# POWER.net
KiCad netlist of a schematic drawn in Altium Designer
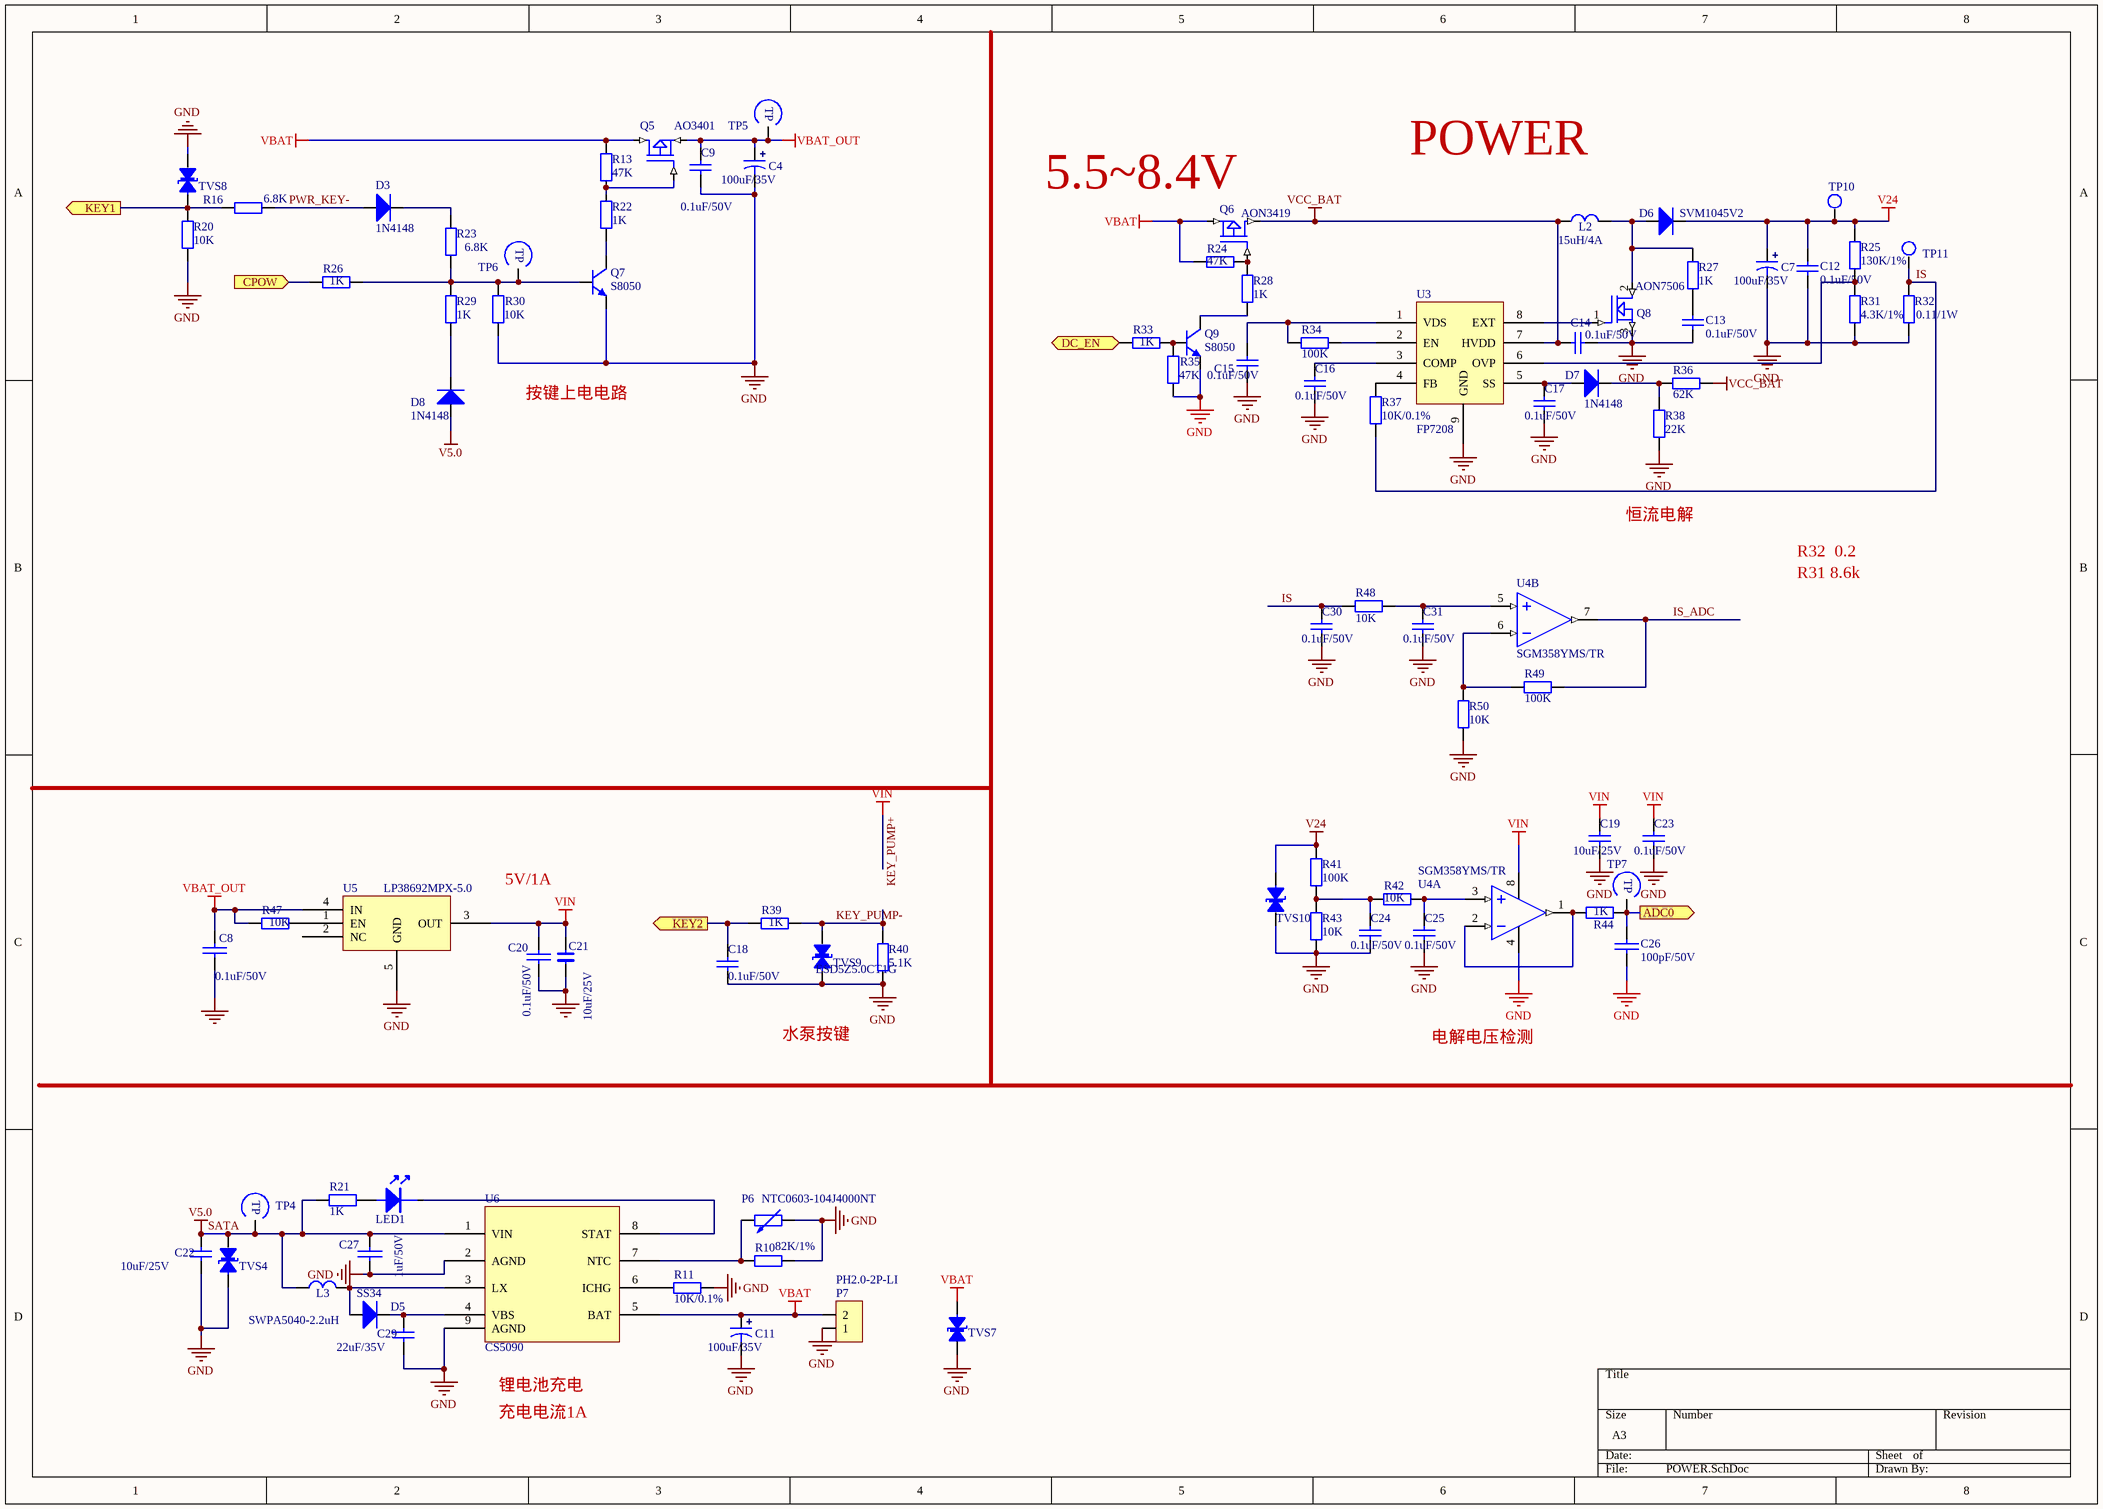
[diagram p0: POWER.SchDoc]

(export (version "E")
  (design (tool "Eeschema 10.0.6"))
  (components
    (comp (ref "C4")
      (value "100uF/35V")
      (footprint "6*8")
      (description "电解电容")
      (libsource (lib "XiaoyI") (part "CAP2"))
    )
    (comp (ref "C7")
      (value "100uF/35V")
      (footprint "6*8")
      (description "电解电容")
      (libsource (lib "XiaoyI") (part "CAP2"))
    )
    (comp (ref "C8")
      (value "0.1uF/50V")
      (footprint "SMD-0603C")
      (description "Capacitor")
      (libsource (lib "*") (part "CAP"))
    )
    (comp (ref "C9")
      (value "0.1uF/50V")
      (footprint "SMD-0603C")
      (description "贴片电容 10%")
      (libsource (lib "XiaoyI") (part "CAP4"))
    )
    (comp (ref "C11")
      (value "100uF/35V")
      (footprint "6*8")
      (description "电解电容")
      (libsource (lib "XiaoyI") (part "CAP2"))
    )
    (comp (ref "C12")
      (value "0.1uF/50V")
      (footprint "SMD-0603C")
      (description "贴片电容 10%")
      (libsource (lib "XiaoyI") (part "CAP4"))
    )
    (comp (ref "C13")
      (value "0.1uF/50V")
      (footprint "SMD-0603C")
      (description "贴片电容 10%")
      (libsource (lib "XiaoyI") (part "CAP4"))
    )
    (comp (ref "C14")
      (value "0.1uF/50V")
      (footprint "SMD-0603C")
      (description "贴片电容 10%")
      (libsource (lib "XiaoyI") (part "CAP4"))
    )
    (comp (ref "C15")
      (value "0.1uF/50V")
      (footprint "SMD-0603C")
      (description "贴片电容 10%")
      (libsource (lib "XiaoyI") (part "CAP4"))
    )
    (comp (ref "C16")
      (value "0.1uF/50V")
      (footprint "SMD-0603C")
      (description "贴片电容 10%")
      (libsource (lib "XiaoyI") (part "CAP4"))
    )
    (comp (ref "C17")
      (value "0.1uF/50V")
      (footprint "SMD-0603C")
      (description "贴片电容 10%")
      (libsource (lib "XiaoyI") (part "CAP4"))
    )
    (comp (ref "C18")
      (value "0.1uF/50V")
      (footprint "SMD-0603C")
      (description "贴片电容 10%")
      (libsource (lib "XiaoyI") (part "CAP4"))
    )
    (comp (ref "C19")
      (value "10uF/25V")
      (footprint "SMD-0603C")
      (description "贴片电容 10%")
      (libsource (lib "XiaoyI") (part "CAP4"))
    )
    (comp (ref "C20")
      (value "0.1uF/50V")
      (footprint "SMD-0603C")
      (description "Capacitor")
      (libsource (lib "*") (part "CAP"))
    )
    (comp (ref "C21")
      (value "10uF/25V")
      (footprint "SMD-0603C")
      (description "C")
      (libsource (lib "Top") (part "C"))
    )
    (comp (ref "C22")
      (value "10uF/25V")
      (footprint "SMD-0603C")
      (description "贴片电容 20%")
      (libsource (lib "XiaoyI") (part "CAP4"))
    )
    (comp (ref "C23")
      (value "0.1uF/50V")
      (footprint "SMD-0603C")
      (description "贴片电容 10%")
      (libsource (lib "XiaoyI") (part "CAP4"))
    )
    (comp (ref "C24")
      (value "0.1uF/50V")
      (footprint "SMD-0603C")
      (description "贴片电容 10%")
      (libsource (lib "XiaoyI") (part "CAP4"))
    )
    (comp (ref "C25")
      (value "0.1uF/50V")
      (footprint "SMD-0603C")
      (description "贴片电容 10%")
      (libsource (lib "XiaoyI") (part "CAP4"))
    )
    (comp (ref "C26")
      (value "100pF/50V")
      (footprint "SMD-0603C")
      (description "贴片电容 10%")
      (libsource (lib "*") (part "CAP"))
    )
    (comp (ref "C27")
      (value "1uF/50V")
      (footprint "SMD-0603C")
      (description "Capacitor")
      (libsource (lib "*") (part "CAP"))
    )
    (comp (ref "C29")
      (value "22uF/35V")
      (footprint "SMD-0603C")
      (description "贴片电容 10%")
      (libsource (lib "XiaoyI") (part "CAP4"))
    )
    (comp (ref "C30")
      (value "0.1uF/50V")
      (footprint "SMD-0603C")
      (description "贴片电容 10%")
      (libsource (lib "XiaoyI") (part "CAP4"))
    )
    (comp (ref "C31")
      (value "0.1uF/50V")
      (footprint "SMD-0603C")
      (description "贴片电容 10%")
      (libsource (lib "XiaoyI") (part "CAP4"))
    )
    (comp (ref "D3")
      (value "1N4148")
      (footprint "SOD-523")
      (description "小封装二极管")
      (libsource (lib "XiaoyI") (part "DIODE2"))
    )
    (comp (ref "D5")
      (value "SS34")
      (footprint "DO-214-AC")
      (description "肖特基二极管")
      (libsource (lib "XiaoyI") (part "DIODE2"))
    )
    (comp (ref "D6")
      (value "SVM1045V2")
      (footprint "TO227")
      (description "肖特基二极管")
      (libsource (lib "XiaoyI") (part "DIODE2"))
    )
    (comp (ref "D7")
      (value "1N4148")
      (footprint "SOD-523")
      (description "小封装二极管")
      (libsource (lib "XiaoyI") (part "DIODE2"))
    )
    (comp (ref "D8")
      (value "1N4148")
      (footprint "SOD-523")
      (description "小封装二极管")
      (libsource (lib "XiaoyI") (part "DIODE2"))
    )
    (comp (ref "L2")
      (value "15uH/4A")
      (footprint "INDUCTOR7*7")
      (description "10uH 1A")
      (libsource (lib "XiaoyI") (part "Inductor1"))
    )
    (comp (ref "L3")
      (value "SWPA5040-2.2uH")
      (footprint "INDUCTOR_5*5")
      (description "10uH 1A")
      (libsource (lib "XiaoyI") (part "Inductor1"))
    )
    (comp (ref "LED1")
      (value "蓝光 3528")
      (footprint "SMD-0603D")
      (description "LED 3528 蓝")
      (libsource (lib "XiaoyI") (part "LED0"))
    )
    (comp (ref "P6")
      (value "NTC0603-104J4000NT")
      (footprint "SMD-0603")
      (description "卧贴")
      (libsource (lib "ABB") (part "RES3"))
    )
    (comp (ref "P7")
      (value "PH2.0-2P-LI")
      (footprint "PH2.0-2P-LI")
      (description "间距2.0mm 立贴 2Pin")
      (libsource (lib "XiaoyI") (part "SIP-2"))
    )
    (comp (ref "Q5")
      (value "AO3401")
      (footprint "SOT-23")
      (description "MOSFET P")
      (libsource (lib "ABB") (part "MOSFET P"))
    )
    (comp (ref "Q6")
      (value "AON3419")
      (footprint "DFN3*3-8")
      (description "MOSFET-P")
      (libsource (lib "XiaoyI") (part "MOSFET-P-B"))
    )
    (comp (ref "Q7")
      (value "S8050")
      (footprint "SOT-23")
      (description "NPN")
      (libsource (lib "XiaoyI") (part "NPN-1"))
    )
    (comp (ref "Q8")
      (value "AON7506")
      (footprint "DFN3*3-8")
      (description "MOSFET N")
      (libsource (lib "XiaoyI") (part "MOSFET N"))
    )
    (comp (ref "Q9")
      (value "S8050")
      (footprint "SOT-23")
      (description "NPN")
      (libsource (lib "XiaoyI") (part "NPN-1"))
    )
    (comp (ref "R10")
      (value "82K/1%")
      (footprint "SMD-0603")
      (description "贴片电阻 1%")
      (libsource (lib "") (part "RES2_3"))
    )
    (comp (ref "R11")
      (value "10K/0.1%")
      (footprint "SMD-0603")
      (description "贴片电阻 1%")
      (libsource (lib "") (part "RES2_3"))
    )
    (comp (ref "R13")
      (value "47K")
      (footprint "SMD-0603")
      (description "贴片电阻 5%")
      (libsource (lib "") (part "RES2_1"))
    )
    (comp (ref "R16")
      (value "6.8K")
      (footprint "SMD-0603")
      (description "贴片电阻 5%")
      (libsource (lib "") (part "RES2_2"))
    )
    (comp (ref "R20")
      (value "10K")
      (footprint "SMD-0603")
      (description "贴片电阻 5%")
      (libsource (lib "XiaoyI") (part "RES2"))
    )
    (comp (ref "R21")
      (value "1K")
      (footprint "SMD-0603")
      (description "贴片电阻 5%")
      (libsource (lib "") (part "RES2_2"))
    )
    (comp (ref "R22")
      (value "1K")
      (footprint "SMD-0603")
      (description "贴片电阻 5%")
      (libsource (lib "XiaoyI") (part "RES2"))
    )
    (comp (ref "R23")
      (value "6.8K")
      (footprint "SMD-0603")
      (description "贴片电阻 5%")
      (libsource (lib "XiaoyI") (part "RES2"))
    )
    (comp (ref "R24")
      (value "47K")
      (footprint "SMD-0603")
      (description "贴片电阻 5%")
      (libsource (lib "") (part "RES2_2"))
    )
    (comp (ref "R25")
      (value "130K/1%")
      (footprint "SMD-0603")
      (description "贴片电阻 5%")
      (libsource (lib "") (part "RES2_1"))
    )
    (comp (ref "R26")
      (value "1K")
      (footprint "SMD-0603")
      (description "贴片电阻 5%")
      (libsource (lib "") (part "RES2_2"))
    )
    (comp (ref "R27")
      (value "1K")
      (footprint "SMD-0603")
      (description "贴片电阻 5%")
      (libsource (lib "") (part "RES2_1"))
    )
    (comp (ref "R28")
      (value "1K")
      (footprint "SMD-0603")
      (description "贴片电阻 5%")
      (libsource (lib "") (part "RES2_1"))
    )
    (comp (ref "R29")
      (value "1K")
      (footprint "SMD-0603")
      (description "贴片电阻 5%")
      (libsource (lib "XiaoyI") (part "RES2"))
    )
    (comp (ref "R30")
      (value "10K")
      (footprint "SMD-0603")
      (description "贴片电阻 5%")
      (libsource (lib "XiaoyI") (part "RES2"))
    )
    (comp (ref "R31")
      (value "4.3K/1%")
      (footprint "SMD-0603")
      (description "贴片电阻 5%")
      (libsource (lib "") (part "RES2_1"))
    )
    (comp (ref "R32")
      (value "0.11/1W")
      (footprint "2512R")
      (description "贴片电阻 5%")
      (libsource (lib "XiaoyI") (part "RES2"))
    )
    (comp (ref "R33")
      (value "1K")
      (footprint "SMD-0603")
      (description "贴片电阻 5%")
      (libsource (lib "") (part "RES2_2"))
    )
    (comp (ref "R34")
      (value "100K")
      (footprint "SMD-0603")
      (description "贴片电阻 5%")
      (libsource (lib "") (part "RES2_2"))
    )
    (comp (ref "R35")
      (value "47K")
      (footprint "SMD-0603")
      (description "贴片电阻 5%")
      (libsource (lib "XiaoyI") (part "RES2"))
    )
    (comp (ref "R36")
      (value "62K")
      (footprint "SMD-0603")
      (description "贴片电阻 5%")
      (libsource (lib "") (part "RES2_2"))
    )
    (comp (ref "R37")
      (value "10K/0.1%")
      (footprint "SMD-0603")
      (description "贴片电阻 5%")
      (libsource (lib "XiaoyI") (part "RES2"))
    )
    (comp (ref "R38")
      (value "22K")
      (footprint "SMD-0603")
      (description "贴片电阻 5%")
      (libsource (lib "") (part "RES2_1"))
    )
    (comp (ref "R39")
      (value "1K")
      (footprint "SMD-0603")
      (description "贴片电阻 5%")
      (libsource (lib "") (part "RES2_2"))
    )
    (comp (ref "R40")
      (value "5.1K")
      (footprint "SMD-0603")
      (description "贴片电阻 5%")
      (libsource (lib "XiaoyI") (part "RES2"))
    )
    (comp (ref "R41")
      (value "100K")
      (footprint "SMD-0603")
      (description "贴片电阻 1%")
      (libsource (lib "") (part "RES0_3"))
    )
    (comp (ref "R42")
      (value "10K")
      (footprint "SMD-0603")
      (description "贴片电阻 5%")
      (libsource (lib "") (part "RES0_1"))
    )
    (comp (ref "R43")
      (value "10K")
      (footprint "SMD-0603")
      (description "贴片电阻 1%")
      (libsource (lib "") (part "RES0_3"))
    )
    (comp (ref "R44")
      (value "1K")
      (footprint "SMD-0603")
      (description "贴片电阻 1%")
      (libsource (lib "") (part "RES2_3"))
    )
    (comp (ref "R47")
      (value "10K")
      (footprint "SMD-0603")
      (description "贴片电阻 5%")
      (libsource (lib "") (part "RES2_2"))
    )
    (comp (ref "R48")
      (value "10K")
      (footprint "SMD-0603")
      (description "贴片电阻 5%")
      (libsource (lib "") (part "RES0_1"))
    )
    (comp (ref "R49")
      (value "100K")
      (footprint "SMD-0603")
      (description "贴片电阻 5%")
      (libsource (lib "") (part "RES0_2"))
    )
    (comp (ref "R50")
      (value "10K")
      (footprint "SMD-0603")
      (description "贴片电阻 5%")
      (libsource (lib "ABB") (part "RES0"))
    )
    (comp (ref "TP4")
      (value "testpoint")
      (footprint "TP")
      (description "测试点")
      (libsource (lib "XiaoyI") (part "TP-1"))
    )
    (comp (ref "TP5")
      (value "testpoint")
      (footprint "TP")
      (description "测试点")
      (libsource (lib "XiaoyI") (part "TP-1"))
    )
    (comp (ref "TP6")
      (value "testpoint")
      (footprint "TP")
      (description "测试点")
      (libsource (lib "XiaoyI") (part "TP-1"))
    )
    (comp (ref "TP7")
      (value "testpoint")
      (footprint "TP")
      (description "测试点")
      (libsource (lib "XiaoyI") (part "TP-1"))
    )
    (comp (ref "TP10") (value "TPS") (footprint "HOLE") (libsource (lib "stm32") (part "TPS")))
    (comp (ref "TP11") (value "TPS") (footprint "HOLE") (libsource (lib "stm32") (part "TPS")))
    (comp (ref "TVS4")
      (value "ESD5Z5.0CT1G")
      (footprint "SOD-523")
      (description "ESD二极管")
      (libsource (lib "XiaoyI") (part "TVS-1"))
    )
    (comp (ref "TVS7")
      (value "SMF12CA")
      (footprint "SOD-123")
      (description "ESD二极管")
      (libsource (lib "") (part "TVS-1_1"))
    )
    (comp (ref "TVS8")
      (value "ESD5Z5.0CT1G")
      (footprint "SOD-523")
      (description "ESD二极管")
      (libsource (lib "XiaoyI") (part "TVS-1"))
    )
    (comp (ref "TVS9")
      (value "ESD5Z5.0CT1G")
      (footprint "SOD-523")
      (description "ESD二极管")
      (libsource (lib "XiaoyI") (part "TVS-1"))
    )
    (comp (ref "TVS10")
      (value "SMF24CA")
      (footprint "SOD-123")
      (description "ESD二极管")
      (libsource (lib "") (part "TVS-1_1"))
    )
    (comp (ref "U3")
      (value "FP7208")
      (footprint "SOP127P600X265_HS-9N")
      (libsource (lib "电解水杯V1.1_ZM_20210702") (part "FP7208"))
    )
    (comp (ref "U4")
      (value "SGM358YMS/TR")
      (footprint "MSOP-8")
      (description "运放")
      (libsource (lib "电解水杯V1.1_ZM_20210702") (part "LM358"))
    )
    (comp (ref "U5")
      (value "LP38692MPX-5.0")
      (footprint "SOT223-5")
      (libsource (lib "stm32") (part "LP38692MPX-5.0"))
    )
    (comp (ref "U6")
      (value "CS5090")
      (footprint "SOP127P600X265_HS-9N")
      (libsource (lib "电解水杯V1.1_ZM_20210702") (part "CS5095E"))
    )
  )
  (nets
    (net (code "1") (name "/ADC0") (class "Default")
      (node (ref "C26") (pin "1") (pinfunction "1_1") (pintype "passive"))
      (node (ref "R44") (pin "1") (pinfunction "1_1") (pintype "passive"))
      (node (ref "TP7") (pin "1") (pinfunction "1_1") (pintype "passive"))
    )
    (net (code "2") (name "/CPOW") (class "Default")
      (node (ref "R26") (pin "1") (pinfunction "1_1") (pintype "passive"))
    )
    (net (code "3") (name "/DC_EN") (class "Default")
      (node (ref "R33") (pin "1") (pinfunction "1_1") (pintype "passive"))
    )
    (net (code "4") (name "/IS") (class "Default")
      (node (ref "C30") (pin "2") (pinfunction "2_2") (pintype "passive"))
      (node (ref "R32") (pin "2") (pinfunction "2_2") (pintype "passive"))
      (node (ref "R37") (pin "1") (pinfunction "1_1") (pintype "passive"))
      (node (ref "R48") (pin "2") (pinfunction "2_2") (pintype "passive"))
      (node (ref "TP11") (pin "1") (pinfunction "1_1") (pintype "passive"))
    )
    (net (code "5") (name "/IS_ADC") (class "Default")
      (node (ref "R49") (pin "2") (pinfunction "2_2") (pintype "passive"))
      (node (ref "U4") (pin "7") (pinfunction "OUT2_7") (pintype "output"))
    )
    (net (code "6") (name "/KEY1") (class "Default")
      (node (ref "R16") (pin "1") (pinfunction "1_1") (pintype "passive"))
      (node (ref "R20") (pin "2") (pinfunction "2_2") (pintype "passive"))
      (node (ref "TVS8") (pin "2") (pinfunction "B_2") (pintype "passive"))
    )
    (net (code "7") (name "/KEY2") (class "Default")
      (node (ref "C18") (pin "2") (pinfunction "2_2") (pintype "passive"))
      (node (ref "R39") (pin "1") (pinfunction "1_1") (pintype "passive"))
    )
    (net (code "8") (name "/KEY_PUMP-") (class "Default")
      (node (ref "R39") (pin "2") (pinfunction "2_2") (pintype "passive"))
      (node (ref "R40") (pin "2") (pinfunction "2_2") (pintype "passive"))
      (node (ref "TVS9") (pin "1") (pinfunction "A_1") (pintype "passive"))
    )
    (net (code "9") (name "/PWR_KEY-") (class "Default")
      (node (ref "D3") (pin "1") (pinfunction "A_1") (pintype "passive"))
      (node (ref "R16") (pin "2") (pinfunction "2_2") (pintype "passive"))
    )
    (net (code "10") (name "GND") (class "Default")
      (node (ref "C11") (pin "2") (pinfunction "2_2") (pintype "passive"))
      (node (ref "C12") (pin "2") (pinfunction "2_2") (pintype "passive"))
      (node (ref "C13") (pin "2") (pinfunction "2_2") (pintype "passive"))
      (node (ref "C14") (pin "1") (pinfunction "1_1") (pintype "passive"))
      (node (ref "C15") (pin "1") (pinfunction "1_1") (pintype "passive"))
      (node (ref "C16") (pin "1") (pinfunction "1_1") (pintype "passive"))
      (node (ref "C17") (pin "1") (pinfunction "1_1") (pintype "passive"))
      (node (ref "C18") (pin "1") (pinfunction "1_1") (pintype "passive"))
      (node (ref "C19") (pin "1") (pinfunction "1_1") (pintype "passive"))
      (node (ref "C20") (pin "2") (pinfunction "2_2") (pintype "passive"))
      (node (ref "C21") (pin "1") (pintype "passive"))
      (node (ref "C22") (pin "1") (pinfunction "1_1") (pintype "passive"))
      (node (ref "C23") (pin "1") (pinfunction "1_1") (pintype "passive"))
      (node (ref "C24") (pin "1") (pinfunction "1_1") (pintype "passive"))
      (node (ref "C25") (pin "1") (pinfunction "1_1") (pintype "passive"))
      (node (ref "C26") (pin "2") (pinfunction "2_2") (pintype "passive"))
      (node (ref "C27") (pin "2") (pinfunction "2_2") (pintype "passive"))
      (node (ref "C29") (pin "1") (pinfunction "1_1") (pintype "passive"))
      (node (ref "C30") (pin "1") (pinfunction "1_1") (pintype "passive"))
      (node (ref "C31") (pin "1") (pinfunction "1_1") (pintype "passive"))
      (node (ref "C4") (pin "2") (pinfunction "2_2") (pintype "passive"))
      (node (ref "C7") (pin "2") (pinfunction "2_2") (pintype "passive"))
      (node (ref "C8") (pin "2") (pinfunction "2_2") (pintype "passive"))
      (node (ref "C9") (pin "1") (pinfunction "1_1") (pintype "passive"))
      (node (ref "P6") (pin "1") (pinfunction "1_1") (pintype "passive"))
      (node (ref "P7") (pin "1") (pinfunction "1_1") (pintype "passive"))
      (node (ref "Q7") (pin "2") (pinfunction "E_2") (pintype "passive"))
      (node (ref "Q8") (pin "3") (pinfunction "S_3") (pintype "output"))
      (node (ref "Q9") (pin "2") (pinfunction "E_2") (pintype "passive"))
      (node (ref "R10") (pin "1") (pinfunction "1_1") (pintype "passive"))
      (node (ref "R11") (pin "1") (pinfunction "1_1") (pintype "passive"))
      (node (ref "R20") (pin "1") (pinfunction "1_1") (pintype "passive"))
      (node (ref "R30") (pin "1") (pinfunction "1_1") (pintype "passive"))
      (node (ref "R31") (pin "2") (pinfunction "2_2") (pintype "passive"))
      (node (ref "R32") (pin "1") (pinfunction "1_1") (pintype "passive"))
      (node (ref "R35") (pin "1") (pinfunction "1_1") (pintype "passive"))
      (node (ref "R38") (pin "2") (pinfunction "2_2") (pintype "passive"))
      (node (ref "R40") (pin "1") (pinfunction "1_1") (pintype "passive"))
      (node (ref "R43") (pin "1") (pinfunction "1_1") (pintype "passive"))
      (node (ref "R50") (pin "2") (pinfunction "2_2") (pintype "passive"))
      (node (ref "TVS10") (pin "1") (pinfunction "A_1") (pintype "passive"))
      (node (ref "TVS4") (pin "2") (pinfunction "B_2") (pintype "passive"))
      (node (ref "TVS7") (pin "1") (pinfunction "A_1") (pintype "passive"))
      (node (ref "TVS8") (pin "1") (pinfunction "A_1") (pintype "passive"))
      (node (ref "TVS9") (pin "2") (pinfunction "B_2") (pintype "passive"))
      (node (ref "U3") (pin "9") (pinfunction "GND_9") (pintype "passive"))
      (node (ref "U4") (pin "4") (pinfunction "V-_4") (pintype "power_in"))
      (node (ref "U5") (pin "5") (pinfunction "GND_5") (pintype "passive"))
      (node (ref "U6") (pin "2") (pinfunction "AGND_2") (pintype "passive"))
      (node (ref "U6") (pin "9") (pinfunction "AGND_9") (pintype "passive"))
    )
    (net (code "11") (name "Net-(C13-Pad1)") (class "Default")
      (node (ref "C13") (pin "1") (pinfunction "1_1") (pintype "passive"))
      (node (ref "R27") (pin "2") (pinfunction "2_2") (pintype "passive"))
    )
    (net (code "12") (name "Net-(C24-Pad2)") (class "Default")
      (node (ref "C24") (pin "2") (pinfunction "2_2") (pintype "passive"))
      (node (ref "R41") (pin "1") (pinfunction "1_1") (pintype "passive"))
      (node (ref "R42") (pin "2") (pinfunction "2_2") (pintype "passive"))
      (node (ref "R43") (pin "2") (pinfunction "2_2") (pintype "passive"))
    )
    (net (code "13") (name "Net-(D3-K)") (class "Default")
      (node (ref "D3") (pin "2") (pinfunction "K_2") (pintype "passive"))
      (node (ref "R23") (pin "2") (pinfunction "2_2") (pintype "passive"))
    )
    (net (code "14") (name "Net-(D5-A)") (class "Default")
      (node (ref "D5") (pin "1") (pinfunction "A_1") (pintype "passive"))
      (node (ref "L3") (pin "2") (pinfunction "2_2") (pintype "passive"))
      (node (ref "U6") (pin "3") (pinfunction "LX_3") (pintype "passive"))
    )
    (net (code "15") (name "Net-(D5-K)") (class "Default")
      (node (ref "C29") (pin "2") (pinfunction "2_2") (pintype "passive"))
      (node (ref "D5") (pin "2") (pinfunction "K_2") (pintype "passive"))
      (node (ref "U6") (pin "4") (pinfunction "VBS_4") (pintype "passive"))
    )
    (net (code "16") (name "Net-(D6-A)") (class "Default")
      (node (ref "D6") (pin "1") (pinfunction "A_1") (pintype "passive"))
      (node (ref "L2") (pin "2") (pinfunction "2_2") (pintype "passive"))
      (node (ref "Q8") (pin "2") (pinfunction "D_2") (pintype "input"))
      (node (ref "R27") (pin "1") (pinfunction "1_1") (pintype "passive"))
    )
    (net (code "17") (name "Net-(D7-A)") (class "Default")
      (node (ref "C17") (pin "2") (pinfunction "2_2") (pintype "passive"))
      (node (ref "D7") (pin "1") (pinfunction "A_1") (pintype "passive"))
      (node (ref "U3") (pin "5") (pinfunction "SS_5") (pintype "passive"))
    )
    (net (code "18") (name "Net-(D7-K)") (class "Default")
      (node (ref "D7") (pin "2") (pinfunction "K_2") (pintype "passive"))
      (node (ref "R36") (pin "1") (pinfunction "1_1") (pintype "passive"))
      (node (ref "R38") (pin "1") (pinfunction "1_1") (pintype "passive"))
    )
    (net (code "19") (name "Net-(D8-K)") (class "Default")
      (node (ref "D8") (pin "2") (pinfunction "K_2") (pintype "passive"))
      (node (ref "R29") (pin "1") (pinfunction "1_1") (pintype "passive"))
    )
    (net (code "20") (name "Net-(LED1-Pad1)") (class "Default")
      (node (ref "LED1") (pin "1") (pinfunction "1_1") (pintype "passive"))
      (node (ref "R21") (pin "2") (pinfunction "2_2") (pintype "passive"))
    )
    (net (code "21") (name "Net-(Q5-G)") (class "Default")
      (node (ref "Q5") (pin "1") (pinfunction "G_1") (pintype "input"))
      (node (ref "R13") (pin "2") (pinfunction "2_2") (pintype "passive"))
      (node (ref "R22") (pin "2") (pinfunction "2_2") (pintype "passive"))
    )
    (net (code "22") (name "Net-(Q6-G)") (class "Default")
      (node (ref "Q6") (pin "1") (pinfunction "G_1") (pintype "input"))
      (node (ref "R24") (pin "2") (pinfunction "2_2") (pintype "passive"))
      (node (ref "R28") (pin "1") (pinfunction "1_1") (pintype "passive"))
    )
    (net (code "23") (name "Net-(Q7-B)") (class "Default")
      (node (ref "Q7") (pin "1") (pinfunction "B_1") (pintype "passive"))
      (node (ref "R23") (pin "1") (pinfunction "1_1") (pintype "passive"))
      (node (ref "R26") (pin "2") (pinfunction "2_2") (pintype "passive"))
      (node (ref "R29") (pin "2") (pinfunction "2_2") (pintype "passive"))
      (node (ref "R30") (pin "2") (pinfunction "2_2") (pintype "passive"))
      (node (ref "TP6") (pin "1") (pinfunction "1_1") (pintype "passive"))
    )
    (net (code "24") (name "Net-(Q7-C)") (class "Default")
      (node (ref "Q7") (pin "3") (pinfunction "C_3") (pintype "passive"))
      (node (ref "R22") (pin "1") (pinfunction "1_1") (pintype "passive"))
    )
    (net (code "25") (name "Net-(Q8-G)") (class "Default")
      (node (ref "Q8") (pin "1") (pinfunction "G_1") (pintype "input"))
      (node (ref "U3") (pin "8") (pinfunction "EXT_8") (pintype "passive"))
    )
    (net (code "26") (name "Net-(Q9-B)") (class "Default")
      (node (ref "Q9") (pin "1") (pinfunction "B_1") (pintype "passive"))
      (node (ref "R33") (pin "2") (pinfunction "2_2") (pintype "passive"))
      (node (ref "R35") (pin "2") (pinfunction "2_2") (pintype "passive"))
    )
    (net (code "27") (name "Net-(Q9-C)") (class "Default")
      (node (ref "Q9") (pin "3") (pinfunction "C_3") (pintype "passive"))
      (node (ref "R28") (pin "2") (pinfunction "2_2") (pintype "passive"))
    )
    (net (code "28") (name "Net-(U3-COMP)") (class "Default")
      (node (ref "C16") (pin "2") (pinfunction "2_2") (pintype "passive"))
      (node (ref "U3") (pin "3") (pinfunction "COMP_3") (pintype "passive"))
    )
    (net (code "29") (name "Net-(U3-EN)") (class "Default")
      (node (ref "R34") (pin "2") (pinfunction "2_2") (pintype "passive"))
      (node (ref "U3") (pin "2") (pinfunction "EN_2") (pintype "passive"))
    )
    (net (code "30") (name "Net-(U3-FB)") (class "Default")
      (node (ref "R37") (pin "2") (pinfunction "2_2") (pintype "passive"))
      (node (ref "U3") (pin "4") (pinfunction "FB_4") (pintype "passive"))
    )
    (net (code "31") (name "Net-(U3-OVP)") (class "Default")
      (node (ref "R25") (pin "2") (pinfunction "2_2") (pintype "passive"))
      (node (ref "R31") (pin "1") (pinfunction "1_1") (pintype "passive"))
      (node (ref "U3") (pin "6") (pinfunction "OVP_6") (pintype "passive"))
    )
    (net (code "32") (name "Net-(U3-VDS)") (class "Default")
      (node (ref "C15") (pin "2") (pinfunction "2_2") (pintype "passive"))
      (node (ref "R34") (pin "1") (pinfunction "1_1") (pintype "passive"))
      (node (ref "U3") (pin "1") (pinfunction "VDS_1") (pintype "passive"))
    )
    (net (code "33") (name "Net-(U4A-IN1+)") (class "Default")
      (node (ref "C25") (pin "2") (pinfunction "2_2") (pintype "passive"))
      (node (ref "R42") (pin "1") (pinfunction "1_1") (pintype "passive"))
      (node (ref "U4") (pin "3") (pinfunction "IN1+_3") (pintype "input"))
    )
    (net (code "34") (name "Net-(U4A-IN1-)") (class "Default")
      (node (ref "R44") (pin "2") (pinfunction "2_2") (pintype "passive"))
      (node (ref "U4") (pin "1") (pinfunction "OUT1_1") (pintype "output"))
      (node (ref "U4") (pin "2") (pinfunction "IN1-_2") (pintype "input"))
    )
    (net (code "35") (name "Net-(U4B-IN2+)") (class "Default")
      (node (ref "C31") (pin "2") (pinfunction "2_2") (pintype "passive"))
      (node (ref "R48") (pin "1") (pinfunction "1_1") (pintype "passive"))
      (node (ref "U4") (pin "5") (pinfunction "IN2+_5") (pintype "input"))
    )
    (net (code "36") (name "Net-(U4B-IN2-)") (class "Default")
      (node (ref "R49") (pin "1") (pinfunction "1_1") (pintype "passive"))
      (node (ref "R50") (pin "1") (pinfunction "1_1") (pintype "passive"))
      (node (ref "U4") (pin "6") (pinfunction "IN2-_6") (pintype "input"))
    )
    (net (code "37") (name "Net-(U5-EN)") (class "Default")
      (node (ref "R47") (pin "2") (pinfunction "2_2") (pintype "passive"))
      (node (ref "U5") (pin "1") (pinfunction "EN_1") (pintype "passive"))
    )
    (net (code "38") (name "Net-(U6-ICHG)") (class "Default")
      (node (ref "R11") (pin "2") (pinfunction "2_2") (pintype "passive"))
      (node (ref "U6") (pin "6") (pinfunction "ICHG_6") (pintype "passive"))
    )
    (net (code "39") (name "Net-(U6-NTC)") (class "Default")
      (node (ref "P6") (pin "2") (pinfunction "2_2") (pintype "passive"))
      (node (ref "R10") (pin "2") (pinfunction "2_2") (pintype "passive"))
      (node (ref "U6") (pin "7") (pinfunction "NTC_7") (pintype "passive"))
    )
    (net (code "40") (name "Net-(U6-STAT)") (class "Default")
      (node (ref "LED1") (pin "2") (pinfunction "2_2") (pintype "passive"))
      (node (ref "U6") (pin "8") (pinfunction "STAT_8") (pintype "passive"))
    )
    (net (code "41") (name "V5.0") (class "Default")
      (node (ref "C22") (pin "2") (pinfunction "2_2") (pintype "passive"))
      (node (ref "C27") (pin "1") (pinfunction "1_1") (pintype "passive"))
      (node (ref "D8") (pin "1") (pinfunction "A_1") (pintype "passive"))
      (node (ref "L3") (pin "1") (pinfunction "1_1") (pintype "passive"))
      (node (ref "R21") (pin "1") (pinfunction "1_1") (pintype "passive"))
      (node (ref "TP4") (pin "1") (pinfunction "1_1") (pintype "passive"))
      (node (ref "TVS4") (pin "1") (pinfunction "A_1") (pintype "passive"))
      (node (ref "U6") (pin "1") (pinfunction "VIN_1") (pintype "passive"))
    )
    (net (code "42") (name "V24") (class "Default")
      (node (ref "C12") (pin "1") (pinfunction "1_1") (pintype "passive"))
      (node (ref "C7") (pin "1") (pinfunction "1_1") (pintype "passive"))
      (node (ref "D6") (pin "2") (pinfunction "K_2") (pintype "passive"))
      (node (ref "R25") (pin "1") (pinfunction "1_1") (pintype "passive"))
      (node (ref "R41") (pin "2") (pinfunction "2_2") (pintype "passive"))
      (node (ref "TP10") (pin "1") (pinfunction "1_1") (pintype "passive"))
      (node (ref "TVS10") (pin "2") (pinfunction "B_2") (pintype "passive"))
    )
    (net (code "43") (name "VBAT") (class "Default")
      (node (ref "C11") (pin "1") (pinfunction "1_1") (pintype "passive"))
      (node (ref "P7") (pin "2") (pinfunction "2_2") (pintype "passive"))
      (node (ref "Q5") (pin "2") (pinfunction "D_2") (pintype "input"))
      (node (ref "Q6") (pin "3") (pinfunction "S_3") (pintype "input"))
      (node (ref "R13") (pin "1") (pinfunction "1_1") (pintype "passive"))
      (node (ref "R24") (pin "1") (pinfunction "1_1") (pintype "passive"))
      (node (ref "TVS7") (pin "2") (pinfunction "B_2") (pintype "passive"))
      (node (ref "U6") (pin "5") (pinfunction "BAT_5") (pintype "passive"))
    )
    (net (code "44") (name "VBAT_OUT") (class "Default")
      (node (ref "C4") (pin "1") (pinfunction "1_1") (pintype "passive"))
      (node (ref "C8") (pin "1") (pinfunction "1_1") (pintype "passive"))
      (node (ref "C9") (pin "2") (pinfunction "2_2") (pintype "passive"))
      (node (ref "Q5") (pin "3") (pinfunction "S_3") (pintype "input"))
      (node (ref "R47") (pin "1") (pinfunction "1_1") (pintype "passive"))
      (node (ref "TP5") (pin "1") (pinfunction "1_1") (pintype "passive"))
      (node (ref "U5") (pin "4") (pinfunction "IN_4") (pintype "passive"))
    )
    (net (code "45") (name "VCC_BAT") (class "Default")
      (node (ref "C14") (pin "2") (pinfunction "2_2") (pintype "passive"))
      (node (ref "L2") (pin "1") (pinfunction "1_1") (pintype "passive"))
      (node (ref "Q6") (pin "2") (pinfunction "D_2") (pintype "output"))
      (node (ref "R36") (pin "2") (pinfunction "2_2") (pintype "passive"))
      (node (ref "U3") (pin "7") (pinfunction "HVDD_7") (pintype "passive"))
    )
    (net (code "46") (name "VIN") (class "Default")
      (node (ref "C19") (pin "2") (pinfunction "2_2") (pintype "passive"))
      (node (ref "C20") (pin "1") (pinfunction "1_1") (pintype "passive"))
      (node (ref "C21") (pin "2") (pintype "passive"))
      (node (ref "C23") (pin "2") (pinfunction "2_2") (pintype "passive"))
      (node (ref "U4") (pin "8") (pinfunction "V+_8") (pintype "power_in"))
      (node (ref "U5") (pin "3") (pinfunction "OUT_3") (pintype "passive"))
    )
    (net (code "47") (name "unconnected-(U5-NC-Pad2)") (class "Default")
      (node (ref "U5") (pin "2") (pinfunction "NC_2") (pintype "passive"))
    )
  )
)
